# sensing_unit_rev1.net
KiCad netlist of a schematic drawn in EAGLE
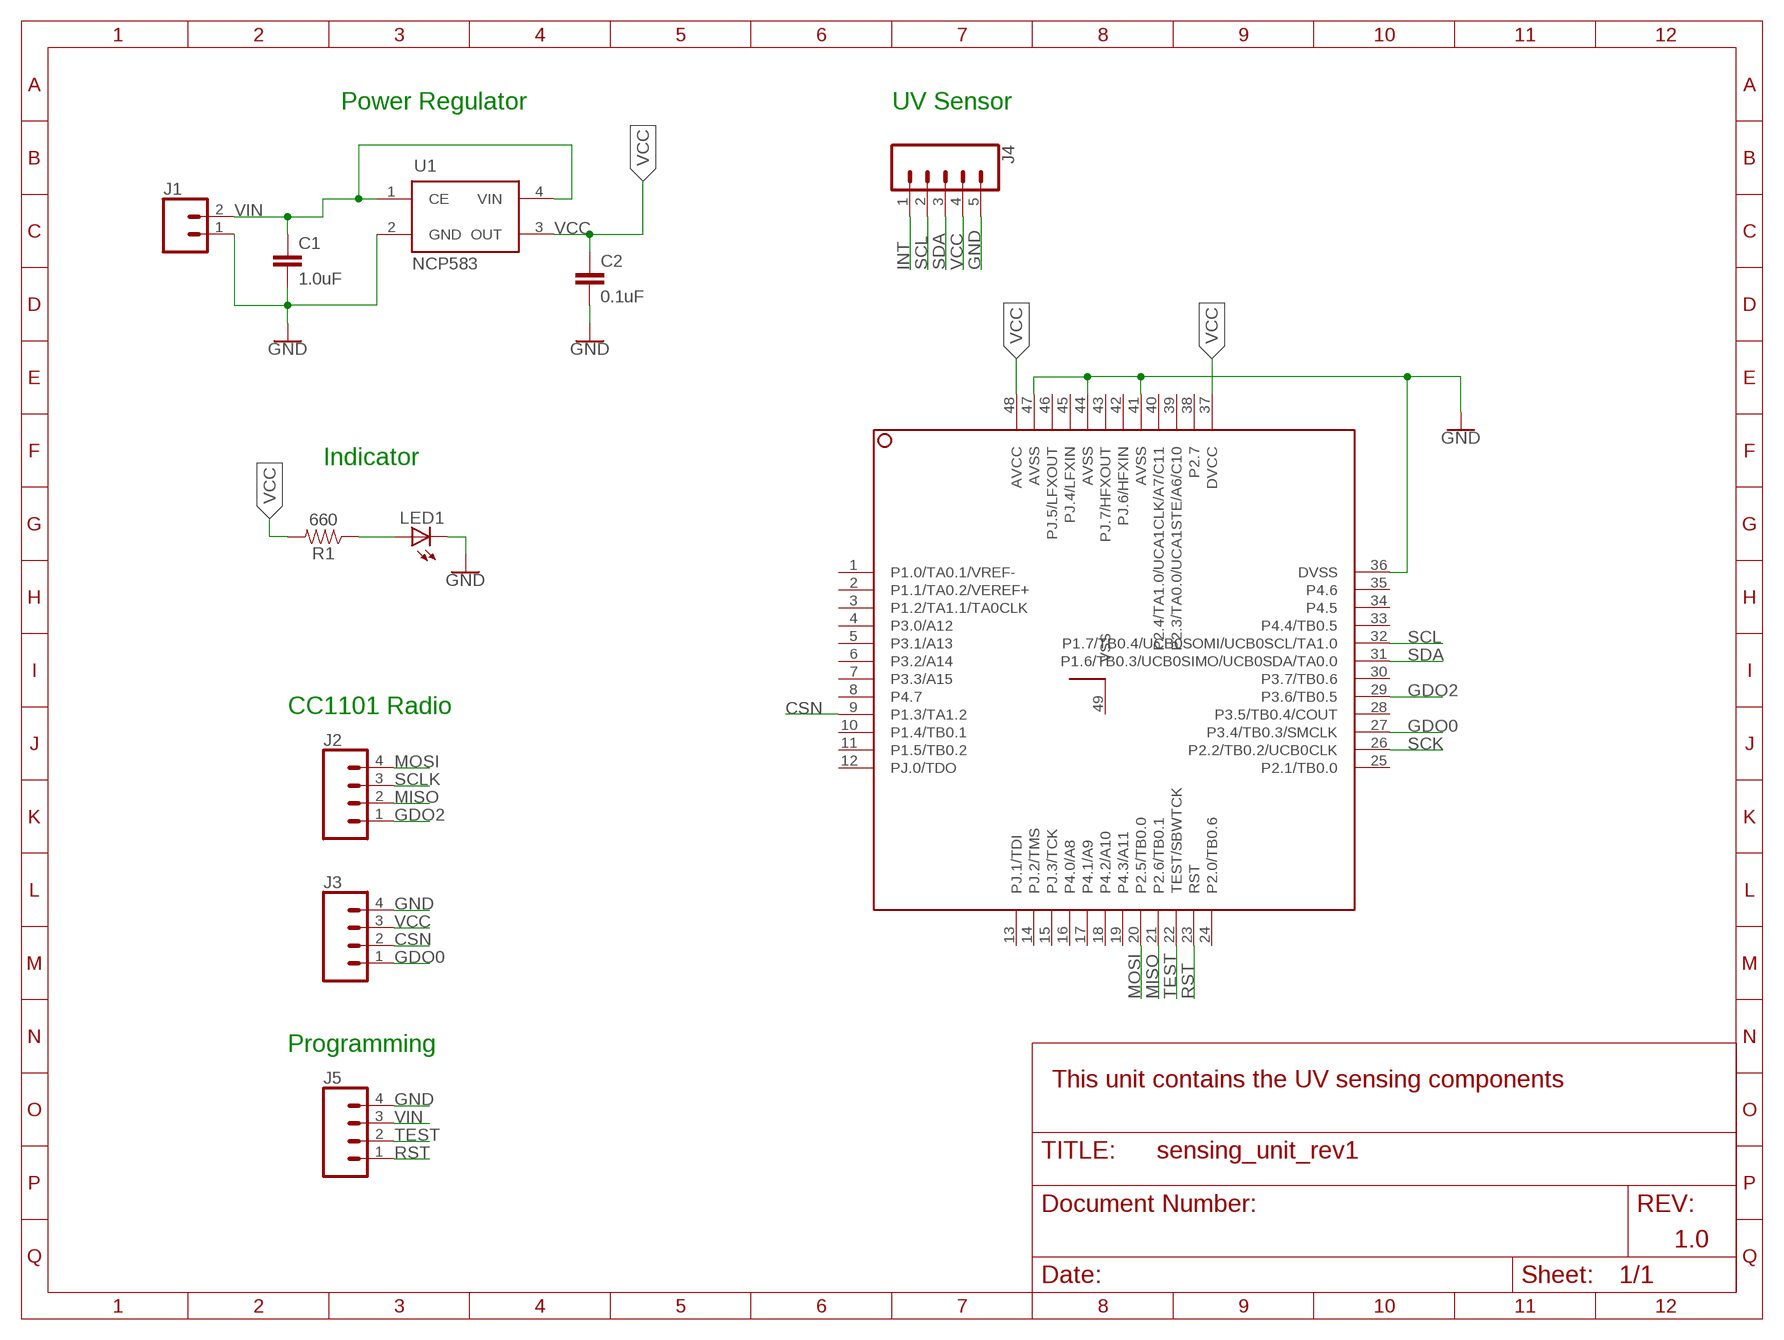
[diagram p0: schematic, sheet 1]

(export (version "E")
  (design (tool "Eeschema 10.0.6"))
  (components
    (comp (ref "C1")
      (value "1.0uF")
      (footprint "eagle-import:0805")
      (libsource (lib "eagle-import") (part "1.0UF-0805-25V-(+80/-20%)"))
    )
    (comp (ref "C2")
      (value "0.1uF")
      (footprint "eagle-import:0805")
      (libsource (lib "eagle-import") (part "1.0UF-0805-25V-(+80/-20%)"))
    )
    (comp (ref "J1")
      (value "CONN_02")
      (footprint "eagle-import:1X02")
      (libsource (lib "eagle-import") (part "CONN_02"))
    )
    (comp (ref "J2")
      (value "CONN_04")
      (footprint "eagle-import:1X04")
      (libsource (lib "eagle-import") (part "CONN_04"))
    )
    (comp (ref "J3")
      (value "CONN_04")
      (footprint "eagle-import:1X04")
      (libsource (lib "eagle-import") (part "CONN_04"))
    )
    (comp (ref "J4")
      (value "CONN_05")
      (footprint "eagle-import:1X05")
      (libsource (lib "eagle-import") (part "CONN_05"))
    )
    (comp (ref "J5")
      (value "CONN_04")
      (footprint "eagle-import:1X04")
      (libsource (lib "eagle-import") (part "CONN_04"))
    )
    (comp (ref "LED1")
      (value "LEDCHIP-LED0805")
      (footprint "eagle-import:CHIP-LED0805")
      (libsource (lib "eagle-import") (part "LEDCHIP-LED0805"))
    )
    (comp (ref "R1")
      (value "660")
      (footprint "eagle-import:0805")
      (libsource (lib "eagle-import") (part "RESISTOR0805"))
    )
    (comp (ref "U1")
      (value "NCP583")
      (footprint "eagle-import:SC82-AB_1PRIMARY")
      (libsource (lib "eagle-import") (part "NCP583"))
    )
    (comp (ref "U2")
      (value "MSP430FR5969_RGZ_48")
      (footprint "eagle-import:RGZ48_4P1X4P1")
      (fields (field (name "MANUFACTURER_PART_NUMBER") "msp430fr5969_rgz_48"))
      (libsource (lib "eagle-import") (part "MSP430FR5969_RGZ_48"))
    )
  )
  (nets
    (net (code "1") (name "/CSN") (class "Default")
      (node (ref "J3") (pin "2") (pinfunction "2_2") (pintype "passive"))
      (node (ref "U2") (pin "9") (pinfunction "P1.3/TA1.2_9") (pintype "bidirectional"))
    )
    (net (code "2") (name "/GDO0") (class "Default")
      (node (ref "J3") (pin "1") (pinfunction "1_1") (pintype "passive"))
      (node (ref "U2") (pin "27") (pinfunction "P3.4/TB0.3/SMCLK_27") (pintype "bidirectional"))
    )
    (net (code "3") (name "/GDO2") (class "Default")
      (node (ref "J2") (pin "1") (pinfunction "1_1") (pintype "passive"))
      (node (ref "U2") (pin "29") (pinfunction "P3.6/TB0.5_29") (pintype "bidirectional"))
    )
    (net (code "4") (name "/INT") (class "Default")
      (node (ref "J4") (pin "1") (pinfunction "1_1") (pintype "passive"))
    )
    (net (code "5") (name "/MISO") (class "Default")
      (node (ref "J2") (pin "2") (pinfunction "2_2") (pintype "passive"))
      (node (ref "U2") (pin "21") (pinfunction "P2.6/TB0.1_21") (pintype "bidirectional"))
    )
    (net (code "6") (name "/MOSI") (class "Default")
      (node (ref "J2") (pin "4") (pinfunction "4_4") (pintype "passive"))
      (node (ref "U2") (pin "20") (pinfunction "P2.5/TB0.0_20") (pintype "bidirectional"))
    )
    (net (code "7") (name "/RST") (class "Default")
      (node (ref "J5") (pin "1") (pinfunction "1_1") (pintype "passive"))
      (node (ref "U2") (pin "23") (pinfunction "RST_23") (pintype "bidirectional"))
    )
    (net (code "8") (name "/SCK") (class "Default")
      (node (ref "U2") (pin "26") (pinfunction "P2.2/TB0.2/UCB0CLK_26") (pintype "bidirectional"))
    )
    (net (code "9") (name "/SCL") (class "Default")
      (node (ref "J4") (pin "2") (pinfunction "2_2") (pintype "passive"))
      (node (ref "U2") (pin "32") (pinfunction "P1.7/TB0.4/UCB0SOMI/UCB0SCL/TA1.0_32") (pintype "bidirectional"))
    )
    (net (code "10") (name "/SCLK") (class "Default")
      (node (ref "J2") (pin "3") (pinfunction "3_3") (pintype "passive"))
    )
    (net (code "11") (name "/SDA") (class "Default")
      (node (ref "J4") (pin "3") (pinfunction "3_3") (pintype "passive"))
      (node (ref "U2") (pin "31") (pinfunction "P1.6/TB0.3/UCB0SIMO/UCB0SDA/TA0.0_31") (pintype "bidirectional"))
    )
    (net (code "12") (name "/TEST") (class "Default")
      (node (ref "J5") (pin "2") (pinfunction "2_2") (pintype "passive"))
      (node (ref "U2") (pin "22") (pinfunction "TEST/SBWTCK_22") (pintype "bidirectional"))
    )
    (net (code "13") (name "/VIN") (class "Default")
      (node (ref "C1") (pin "1") (pinfunction "1_1") (pintype "passive"))
      (node (ref "J1") (pin "2") (pinfunction "2_2") (pintype "passive"))
      (node (ref "J5") (pin "3") (pinfunction "3_3") (pintype "passive"))
      (node (ref "U1") (pin "1") (pinfunction "CE_1") (pintype "bidirectional"))
      (node (ref "U1") (pin "4") (pinfunction "VIN_4") (pintype "bidirectional"))
    )
    (net (code "14") (name "GND") (class "Default")
      (node (ref "C1") (pin "2") (pinfunction "2_2") (pintype "passive"))
      (node (ref "C2") (pin "2") (pinfunction "2_2") (pintype "passive"))
      (node (ref "J1") (pin "1") (pinfunction "1_1") (pintype "passive"))
      (node (ref "J3") (pin "4") (pinfunction "4_4") (pintype "passive"))
      (node (ref "J4") (pin "5") (pinfunction "5_5") (pintype "passive"))
      (node (ref "J5") (pin "4") (pinfunction "4_4") (pintype "passive"))
      (node (ref "LED1") (pin "C") (pinfunction "C_C") (pintype "passive"))
      (node (ref "U1") (pin "2") (pinfunction "GND_2") (pintype "bidirectional"))
      (node (ref "U2") (pin "36") (pinfunction "DVSS_36") (pintype "bidirectional"))
      (node (ref "U2") (pin "41") (pinfunction "AVSS_41") (pintype "bidirectional"))
      (node (ref "U2") (pin "44") (pinfunction "AVSS_44") (pintype "bidirectional"))
      (node (ref "U2") (pin "47") (pinfunction "AVSS_47") (pintype "bidirectional"))
    )
    (net (code "15") (name "Net-(LED1-PadA)") (class "Default")
      (node (ref "LED1") (pin "A") (pinfunction "A_A") (pintype "passive"))
      (node (ref "R1") (pin "1") (pinfunction "1_1") (pintype "passive"))
    )
    (net (code "16") (name "VCC") (class "Default")
      (node (ref "C2") (pin "1") (pinfunction "1_1") (pintype "passive"))
      (node (ref "J3") (pin "3") (pinfunction "3_3") (pintype "passive"))
      (node (ref "J4") (pin "4") (pinfunction "4_4") (pintype "passive"))
      (node (ref "R1") (pin "2") (pinfunction "2_2") (pintype "passive"))
      (node (ref "U1") (pin "3") (pinfunction "OUT_3") (pintype "bidirectional"))
      (node (ref "U2") (pin "37") (pinfunction "DVCC_37") (pintype "bidirectional"))
      (node (ref "U2") (pin "48") (pinfunction "AVCC_48") (pintype "bidirectional"))
    )
    (net (code "17") (name "unconnected-(U2-P1.0{slash}TA0.1{slash}VREF--Pad1)") (class "Default")
      (node (ref "U2") (pin "1") (pinfunction "P1.0/TA0.1/VREF-_1") (pintype "bidirectional"))
    )
    (net (code "18") (name "unconnected-(U2-P1.1{slash}TA0.2{slash}VEREF+-Pad2)") (class "Default")
      (node (ref "U2") (pin "2") (pinfunction "P1.1/TA0.2/VEREF+_2") (pintype "bidirectional"))
    )
    (net (code "19") (name "unconnected-(U2-P1.2{slash}TA1.1{slash}TA0CLK-Pad3)") (class "Default")
      (node (ref "U2") (pin "3") (pinfunction "P1.2/TA1.1/TA0CLK_3") (pintype "bidirectional"))
    )
    (net (code "20") (name "unconnected-(U2-P1.4{slash}TB0.1-Pad10)") (class "Default")
      (node (ref "U2") (pin "10") (pinfunction "P1.4/TB0.1_10") (pintype "bidirectional"))
    )
    (net (code "21") (name "unconnected-(U2-P1.5{slash}TB0.2-Pad11)") (class "Default")
      (node (ref "U2") (pin "11") (pinfunction "P1.5/TB0.2_11") (pintype "bidirectional"))
    )
    (net (code "22") (name "unconnected-(U2-P2.0{slash}TB0.6-Pad24)") (class "Default")
      (node (ref "U2") (pin "24") (pinfunction "P2.0/TB0.6_24") (pintype "bidirectional"))
    )
    (net (code "23") (name "unconnected-(U2-P2.1{slash}TB0.0-Pad25)") (class "Default")
      (node (ref "U2") (pin "25") (pinfunction "P2.1/TB0.0_25") (pintype "bidirectional"))
    )
    (net (code "24") (name "unconnected-(U2-P2.3{slash}TA0.0{slash}UCA1STE{slash}A6{slash}C10-Pad39)") (class "Default")
      (node (ref "U2") (pin "39") (pinfunction "P2.3/TA0.0/UCA1STE/A6/C10_39") (pintype "bidirectional"))
    )
    (net (code "25") (name "unconnected-(U2-P2.4{slash}TA1.0{slash}UCA1CLK{slash}A7{slash}C11-Pad40)") (class "Default")
      (node (ref "U2") (pin "40") (pinfunction "P2.4/TA1.0/UCA1CLK/A7/C11_40") (pintype "bidirectional"))
    )
    (net (code "26") (name "unconnected-(U2-P2.7-Pad38)") (class "Default")
      (node (ref "U2") (pin "38") (pinfunction "P2.7_38") (pintype "bidirectional"))
    )
    (net (code "27") (name "unconnected-(U2-P3.0{slash}A12-Pad4)") (class "Default")
      (node (ref "U2") (pin "4") (pinfunction "P3.0/A12_4") (pintype "bidirectional"))
    )
    (net (code "28") (name "unconnected-(U2-P3.1{slash}A13-Pad5)") (class "Default")
      (node (ref "U2") (pin "5") (pinfunction "P3.1/A13_5") (pintype "bidirectional"))
    )
    (net (code "29") (name "unconnected-(U2-P3.2{slash}A14-Pad6)") (class "Default")
      (node (ref "U2") (pin "6") (pinfunction "P3.2/A14_6") (pintype "bidirectional"))
    )
    (net (code "30") (name "unconnected-(U2-P3.3{slash}A15-Pad7)") (class "Default")
      (node (ref "U2") (pin "7") (pinfunction "P3.3/A15_7") (pintype "bidirectional"))
    )
    (net (code "31") (name "unconnected-(U2-P3.5{slash}TB0.4{slash}COUT-Pad28)") (class "Default")
      (node (ref "U2") (pin "28") (pinfunction "P3.5/TB0.4/COUT_28") (pintype "bidirectional"))
    )
    (net (code "32") (name "unconnected-(U2-P3.7{slash}TB0.6-Pad30)") (class "Default")
      (node (ref "U2") (pin "30") (pinfunction "P3.7/TB0.6_30") (pintype "bidirectional"))
    )
    (net (code "33") (name "unconnected-(U2-P4.0{slash}A8-Pad16)") (class "Default")
      (node (ref "U2") (pin "16") (pinfunction "P4.0/A8_16") (pintype "bidirectional"))
    )
    (net (code "34") (name "unconnected-(U2-P4.1{slash}A9-Pad17)") (class "Default")
      (node (ref "U2") (pin "17") (pinfunction "P4.1/A9_17") (pintype "bidirectional"))
    )
    (net (code "35") (name "unconnected-(U2-P4.2{slash}A10-Pad18)") (class "Default")
      (node (ref "U2") (pin "18") (pinfunction "P4.2/A10_18") (pintype "bidirectional"))
    )
    (net (code "36") (name "unconnected-(U2-P4.3{slash}A11-Pad19)") (class "Default")
      (node (ref "U2") (pin "19") (pinfunction "P4.3/A11_19") (pintype "bidirectional"))
    )
    (net (code "37") (name "unconnected-(U2-P4.4{slash}TB0.5-Pad33)") (class "Default")
      (node (ref "U2") (pin "33") (pinfunction "P4.4/TB0.5_33") (pintype "bidirectional"))
    )
    (net (code "38") (name "unconnected-(U2-P4.5-Pad34)") (class "Default")
      (node (ref "U2") (pin "34") (pinfunction "P4.5_34") (pintype "bidirectional"))
    )
    (net (code "39") (name "unconnected-(U2-P4.6-Pad35)") (class "Default")
      (node (ref "U2") (pin "35") (pinfunction "P4.6_35") (pintype "bidirectional"))
    )
    (net (code "40") (name "unconnected-(U2-P4.7-Pad8)") (class "Default")
      (node (ref "U2") (pin "8") (pinfunction "P4.7_8") (pintype "bidirectional"))
    )
    (net (code "41") (name "unconnected-(U2-PJ.0{slash}TDO-Pad12)") (class "Default")
      (node (ref "U2") (pin "12") (pinfunction "PJ.0/TDO_12") (pintype "bidirectional"))
    )
    (net (code "42") (name "unconnected-(U2-PJ.1{slash}TDI-Pad13)") (class "Default")
      (node (ref "U2") (pin "13") (pinfunction "PJ.1/TDI_13") (pintype "bidirectional"))
    )
    (net (code "43") (name "unconnected-(U2-PJ.2{slash}TMS-Pad14)") (class "Default")
      (node (ref "U2") (pin "14") (pinfunction "PJ.2/TMS_14") (pintype "bidirectional"))
    )
    (net (code "44") (name "unconnected-(U2-PJ.3{slash}TCK-Pad15)") (class "Default")
      (node (ref "U2") (pin "15") (pinfunction "PJ.3/TCK_15") (pintype "bidirectional"))
    )
    (net (code "45") (name "unconnected-(U2-PJ.4{slash}LFXIN-Pad45)") (class "Default")
      (node (ref "U2") (pin "45") (pinfunction "PJ.4/LFXIN_45") (pintype "bidirectional"))
    )
    (net (code "46") (name "unconnected-(U2-PJ.5{slash}LFXOUT-Pad46)") (class "Default")
      (node (ref "U2") (pin "46") (pinfunction "PJ.5/LFXOUT_46") (pintype "bidirectional"))
    )
    (net (code "47") (name "unconnected-(U2-PJ.6{slash}HFXIN-Pad42)") (class "Default")
      (node (ref "U2") (pin "42") (pinfunction "PJ.6/HFXIN_42") (pintype "bidirectional"))
    )
    (net (code "48") (name "unconnected-(U2-PJ.7{slash}HFXOUT-Pad43)") (class "Default")
      (node (ref "U2") (pin "43") (pinfunction "PJ.7/HFXOUT_43") (pintype "bidirectional"))
    )
    (net (code "49") (name "unconnected-(U2-VSS-Pad49)") (class "Default")
      (node (ref "U2") (pin "49") (pinfunction "VSS_49") (pintype "bidirectional"))
    )
  )
)
